# Rauchmelder_2_2B.net
KiCad netlist of a schematic drawn in EAGLE
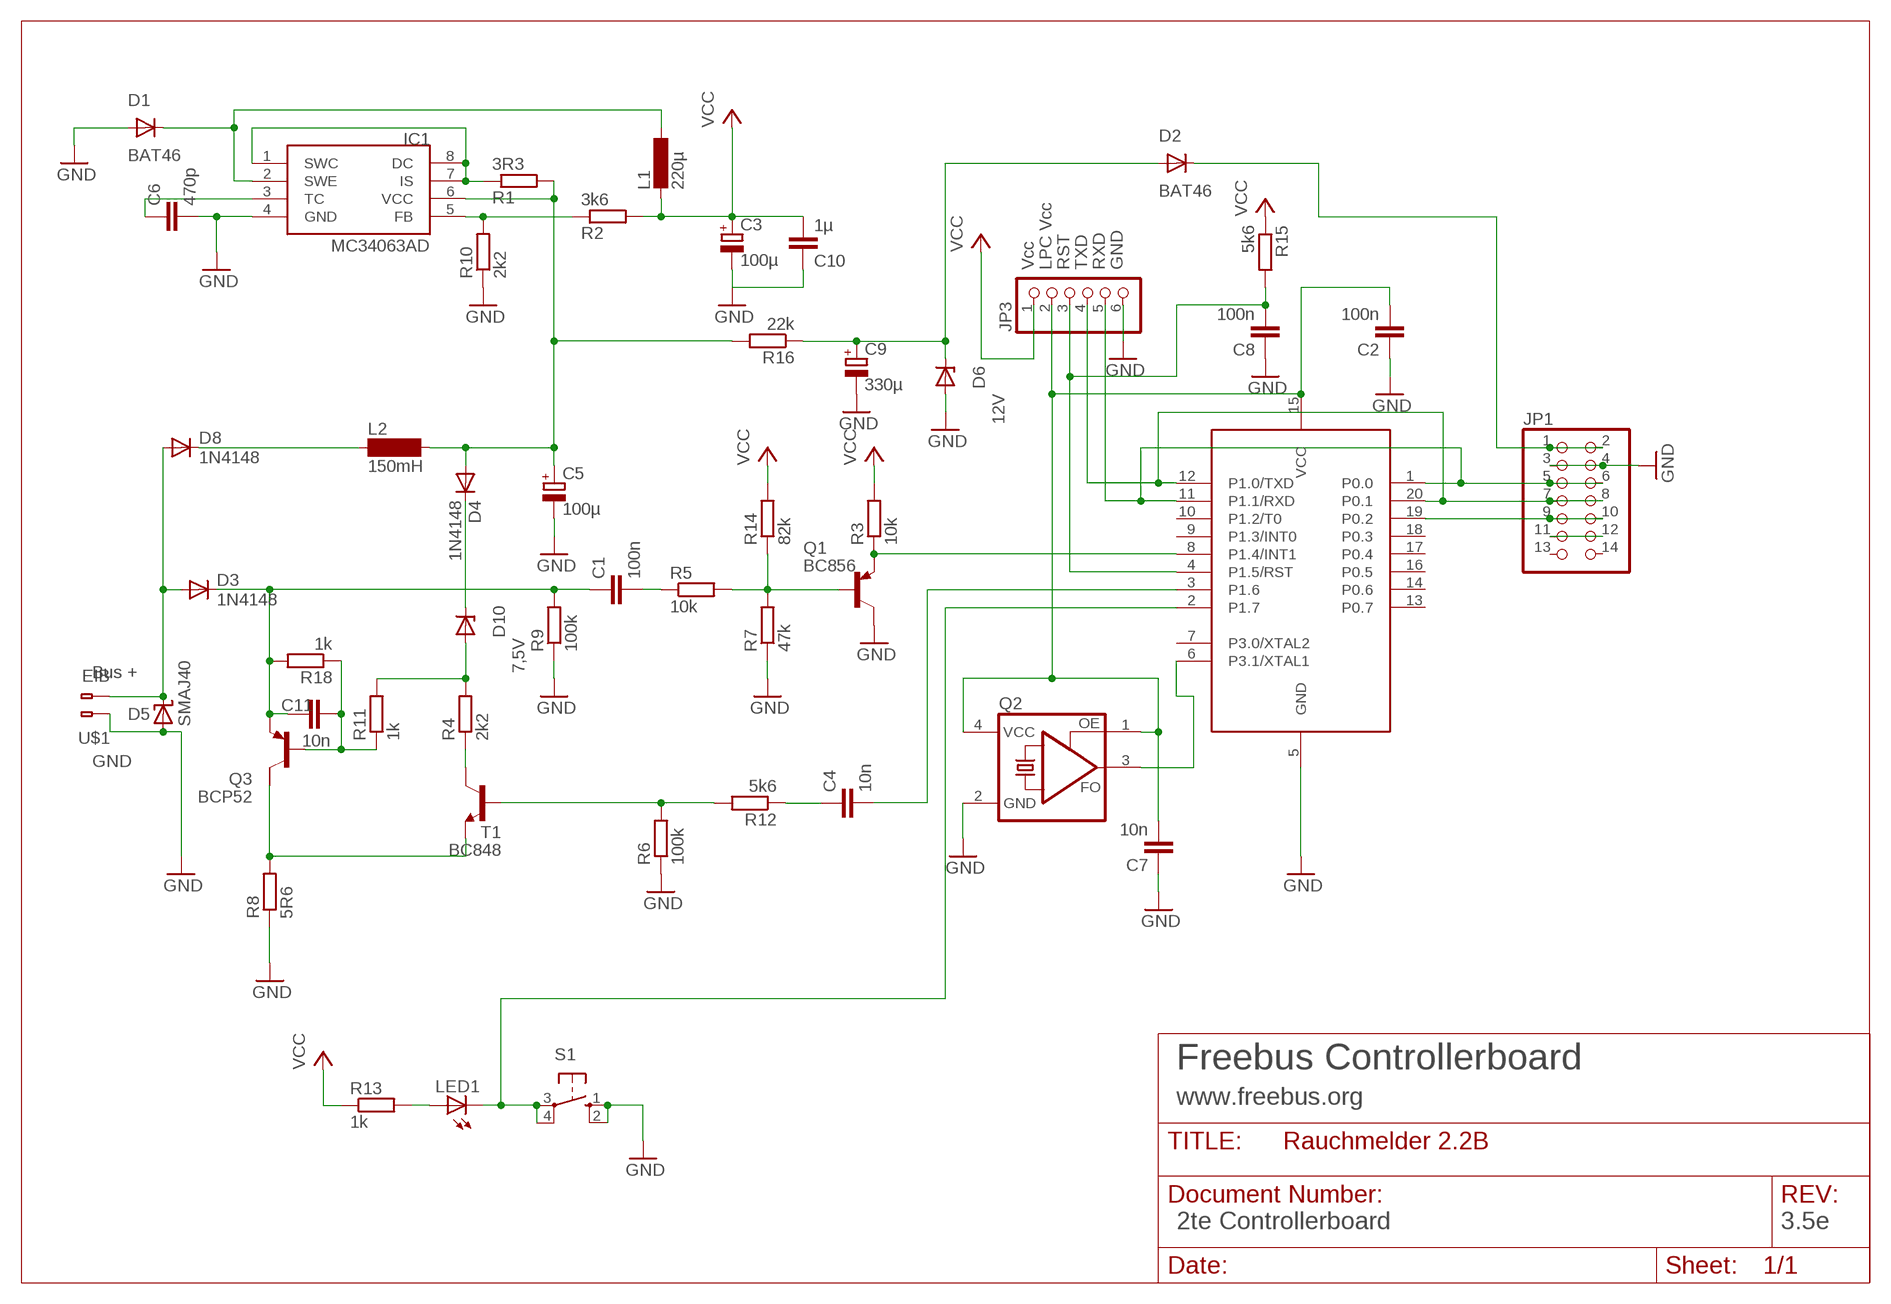
[diagram p0: schematic, sheet 1]

(export (version "E")
  (design (tool "Eeschema 10.0.6"))
  (components
    (comp (ref "C1")
      (value "100n")
      (footprint "eagle-import:C1206")
      (libsource (lib "eagle-import") (part "C-EUC1206"))
    )
    (comp (ref "C2")
      (value "100n")
      (footprint "eagle-import:C1206")
      (libsource (lib "eagle-import") (part "C-EUC1206"))
    )
    (comp (ref "C3")
      (value "100µ")
      (footprint "eagle-import:SANYO-OSCON_SMD_B6")
      (libsource (lib "eagle-import") (part "CPOL-EUSANYO_SMD_B6"))
    )
    (comp (ref "C4")
      (value "10n")
      (footprint "eagle-import:C1206")
      (libsource (lib "eagle-import") (part "C-EUC1206"))
    )
    (comp (ref "C5")
      (value "100µ")
      (footprint "eagle-import:SANYO-OSCON_SMD_C6")
      (libsource (lib "eagle-import") (part "CPOL-EUSANYO_SMD_C6"))
    )
    (comp (ref "C6")
      (value "470p")
      (footprint "eagle-import:C1206")
      (libsource (lib "eagle-import") (part "C-EUC1206"))
    )
    (comp (ref "C7")
      (value "10n")
      (footprint "eagle-import:C1206")
      (libsource (lib "eagle-import") (part "C-EUC1206"))
    )
    (comp (ref "C8")
      (value "100n")
      (footprint "eagle-import:C1206")
      (libsource (lib "eagle-import") (part "C-EUC1206"))
    )
    (comp (ref "C9")
      (value "330µ")
      (footprint "eagle-import:E3,5-8")
      (libsource (lib "eagle-import") (part "CPOL-EUE3.5-8"))
    )
    (comp (ref "C10")
      (value "1µ")
      (footprint "eagle-import:C1206")
      (libsource (lib "eagle-import") (part "C-EUC1206"))
    )
    (comp (ref "C11")
      (value "10n")
      (footprint "eagle-import:C1206")
      (libsource (lib "eagle-import") (part "C-EUC1206"))
    )
    (comp (ref "D1")
      (value "BAT46")
      (footprint "eagle-import:MINIMELF")
      (libsource (lib "eagle-import") (part "DIODE-MINIMELF"))
    )
    (comp (ref "D2")
      (value "BAT46")
      (footprint "eagle-import:MINIMELF")
      (libsource (lib "eagle-import") (part "DIODE-MINIMELF"))
    )
    (comp (ref "D3")
      (value "1N4148")
      (footprint "eagle-import:MINIMELF")
      (libsource (lib "eagle-import") (part "DIODE-MINIMELF"))
    )
    (comp (ref "D4")
      (value "1N4148")
      (footprint "eagle-import:MINIMELF")
      (libsource (lib "eagle-import") (part "DIODE-MINIMELF"))
    )
    (comp (ref "D5")
      (value "SMAJ40")
      (footprint "eagle-import:SMBJ")
      (libsource (lib "eagle-import") (part "SUPPRESSOR-SMBJ"))
    )
    (comp (ref "D6")
      (value "12V")
      (footprint "eagle-import:MINIMELF")
      (libsource (lib "eagle-import") (part "ZPD"))
    )
    (comp (ref "D8")
      (value "1N4148")
      (footprint "eagle-import:MINIMELF")
      (libsource (lib "eagle-import") (part "DIODE-MINIMELF"))
    )
    (comp (ref "D10")
      (value "7,5V")
      (footprint "eagle-import:MINIMELF")
      (libsource (lib "eagle-import") (part "ZPD"))
    )
    (comp (ref "IC1")
      (value "MC34063AD")
      (footprint "eagle-import:SOIC8")
      (libsource (lib "eagle-import") (part "MC34063AD"))
    )
    (comp (ref "IC3")
      (value "LPC922FDH")
      (footprint "eagle-import:TSSOP20")
      (libsource (lib "eagle-import") (part "LPC922FDH"))
    )
    (comp (ref "JP1")
      (value "PINHD-2X7")
      (footprint "eagle-import:2X07")
      (libsource (lib "eagle-import") (part "PINHD-2X7"))
    )
    (comp (ref "JP3")
      (value "PINHD-1X6")
      (footprint "eagle-import:1X06")
      (libsource (lib "eagle-import") (part "PINHD-1X6"))
    )
    (comp (ref "L1")
      (value "220µ")
      (footprint "eagle-import:0207_10")
      (libsource (lib "eagle-import") (part "L-EU0207/10"))
    )
    (comp (ref "L2")
      (value "150mH")
      (footprint "eagle-import:BS11")
      (libsource (lib "eagle-import") (part "BS11"))
    )
    (comp (ref "LED1")
      (value "LED3MM")
      (footprint "eagle-import:LED3MM")
      (libsource (lib "eagle-import") (part "LED3MM"))
    )
    (comp (ref "Q1")
      (value "BC856")
      (footprint "eagle-import:SOT23-BEC")
      (libsource (lib "eagle-import") (part "BC856SMDALT1"))
    )
    (comp (ref "Q2")
      (value "ASFL")
      (footprint "eagle-import:ASF")
      (libsource (lib "eagle-import") (part "ASFL"))
    )
    (comp (ref "Q3")
      (value "BCP52")
      (footprint "eagle-import:SOT223")
      (libsource (lib "eagle-import") (part "FZT753SMD"))
    )
    (comp (ref "R1")
      (value "3R3")
      (footprint "eagle-import:R1206")
      (libsource (lib "eagle-import") (part "R-EU_R1206"))
    )
    (comp (ref "R2")
      (value "3k6")
      (footprint "eagle-import:R1206")
      (libsource (lib "eagle-import") (part "R-EU_R1206"))
    )
    (comp (ref "R3")
      (value "10k")
      (footprint "eagle-import:R1206")
      (libsource (lib "eagle-import") (part "R-EU_R1206"))
    )
    (comp (ref "R4")
      (value "2k2")
      (footprint "eagle-import:R1206")
      (libsource (lib "eagle-import") (part "R-EU_R1206"))
    )
    (comp (ref "R5")
      (value "10k")
      (footprint "eagle-import:R1206")
      (libsource (lib "eagle-import") (part "R-EU_R1206"))
    )
    (comp (ref "R6")
      (value "100k")
      (footprint "eagle-import:R1206")
      (libsource (lib "eagle-import") (part "R-EU_R1206"))
    )
    (comp (ref "R7")
      (value "47k")
      (footprint "eagle-import:R1206")
      (libsource (lib "eagle-import") (part "R-EU_R1206"))
    )
    (comp (ref "R8")
      (value "5R6")
      (footprint "eagle-import:R1206")
      (libsource (lib "eagle-import") (part "R-EU_R1206"))
    )
    (comp (ref "R9")
      (value "100k")
      (footprint "eagle-import:R1206")
      (libsource (lib "eagle-import") (part "R-EU_R1206"))
    )
    (comp (ref "R10")
      (value "2k2")
      (footprint "eagle-import:R1206")
      (libsource (lib "eagle-import") (part "R-EU_R1206"))
    )
    (comp (ref "R11")
      (value "1k")
      (footprint "eagle-import:R1206")
      (libsource (lib "eagle-import") (part "R-EU_R1206"))
    )
    (comp (ref "R12")
      (value "5k6")
      (footprint "eagle-import:R1206")
      (libsource (lib "eagle-import") (part "R-EU_R1206"))
    )
    (comp (ref "R13")
      (value "1k")
      (footprint "eagle-import:R1206")
      (libsource (lib "eagle-import") (part "R-EU_R1206"))
    )
    (comp (ref "R14")
      (value "82k")
      (footprint "eagle-import:R1206")
      (libsource (lib "eagle-import") (part "R-EU_R1206"))
    )
    (comp (ref "R15")
      (value "5k6")
      (footprint "eagle-import:R1206")
      (libsource (lib "eagle-import") (part "R-EU_R1206"))
    )
    (comp (ref "R16")
      (value "22k")
      (footprint "eagle-import:R1206")
      (libsource (lib "eagle-import") (part "R-EU_R1206"))
    )
    (comp (ref "R18")
      (value "1k")
      (footprint "eagle-import:R1206")
      (libsource (lib "eagle-import") (part "R-EU_R1206"))
    )
    (comp (ref "S1")
      (value "10-XX")
      (footprint "eagle-import:B3F-10XX")
      (libsource (lib "eagle-import") (part "10-XX"))
    )
    (comp (ref "T1")
      (value "BC848")
      (footprint "eagle-import:SOT23")
      (libsource (lib "eagle-import") (part "BC848"))
    )
    (comp (ref "U$1")
      (value "EIB")
      (footprint "eagle-import:BUSKLEMME243-724")
      (libsource (lib "eagle-import") (part "EIB"))
    )
  )
  (nets
    (net (code "1") (name "GND") (class "Default")
      (node (ref "C10") (pin "1") (pinfunction "1_1") (pintype "passive"))
      (node (ref "C2") (pin "1") (pinfunction "1_1") (pintype "passive"))
      (node (ref "C3") (pin "-") (pinfunction "-_-") (pintype "passive"))
      (node (ref "C5") (pin "-") (pinfunction "-_-") (pintype "passive"))
      (node (ref "C6") (pin "2") (pinfunction "2_2") (pintype "passive"))
      (node (ref "C7") (pin "1") (pinfunction "1_1") (pintype "passive"))
      (node (ref "C8") (pin "1") (pinfunction "1_1") (pintype "passive"))
      (node (ref "C9") (pin "-") (pinfunction "-_-") (pintype "passive"))
      (node (ref "D1") (pin "A") (pinfunction "A_A") (pintype "passive"))
      (node (ref "D5") (pin "A") (pinfunction "A_A") (pintype "passive"))
      (node (ref "D6") (pin "A") (pinfunction "A_A") (pintype "passive"))
      (node (ref "IC1") (pin "4") (pinfunction "GND_4") (pintype "passive"))
      (node (ref "IC3") (pin "5") (pinfunction "GND_5") (pintype "bidirectional"))
      (node (ref "JP1") (pin "3") (pinfunction "3_3") (pintype "passive"))
      (node (ref "JP1") (pin "4") (pinfunction "4_4") (pintype "passive"))
      (node (ref "JP3") (pin "6") (pinfunction "6_6") (pintype "passive"))
      (node (ref "Q1") (pin "C") (pinfunction "C_C") (pintype "passive"))
      (node (ref "Q2") (pin "2") (pinfunction "GND_2") (pintype "power_in"))
      (node (ref "R10") (pin "1") (pinfunction "1_1") (pintype "passive"))
      (node (ref "R6") (pin "1") (pinfunction "1_1") (pintype "passive"))
      (node (ref "R7") (pin "1") (pinfunction "1_1") (pintype "passive"))
      (node (ref "R8") (pin "1") (pinfunction "1_1") (pintype "passive"))
      (node (ref "R9") (pin "1") (pinfunction "1_1") (pintype "passive"))
      (node (ref "S1") (pin "1") (pinfunction "S_1") (pintype "passive"))
      (node (ref "S1") (pin "2") (pinfunction "S1_2") (pintype "passive"))
      (node (ref "U$1") (pin "1") (pinfunction "B-1_1") (pintype "passive"))
    )
    (net (code "2") (name "Net-(C1-Pad2)") (class "Default")
      (node (ref "C1") (pin "2") (pinfunction "2_2") (pintype "passive"))
      (node (ref "R5") (pin "1") (pinfunction "1_1") (pintype "passive"))
    )
    (net (code "3") (name "Net-(C4-Pad1)") (class "Default")
      (node (ref "C4") (pin "1") (pinfunction "1_1") (pintype "passive"))
      (node (ref "R12") (pin "1") (pinfunction "1_1") (pintype "passive"))
    )
    (net (code "4") (name "Net-(C9-Pad+)") (class "Default")
      (node (ref "C9") (pin "+") (pinfunction "+_+") (pintype "passive"))
      (node (ref "D2") (pin "A") (pinfunction "A_A") (pintype "passive"))
      (node (ref "D6") (pin "C") (pinfunction "C_C") (pintype "passive"))
      (node (ref "R16") (pin "1") (pinfunction "1_1") (pintype "passive"))
    )
    (net (code "5") (name "Net-(D2-PadC)") (class "Default")
      (node (ref "D2") (pin "C") (pinfunction "C_C") (pintype "passive"))
      (node (ref "JP1") (pin "1") (pinfunction "1_1") (pintype "passive"))
      (node (ref "JP1") (pin "2") (pinfunction "2_2") (pintype "passive"))
    )
    (net (code "6") (name "Net-(D8-PadC)") (class "Default")
      (node (ref "D8") (pin "C") (pinfunction "C_C") (pintype "passive"))
      (node (ref "L2") (pin "1") (pinfunction "1_1") (pintype "passive"))
    )
    (net (code "7") (name "Net-(D10-PadA)") (class "Default")
      (node (ref "D10") (pin "A") (pinfunction "A_A") (pintype "passive"))
      (node (ref "R11") (pin "2") (pinfunction "2_2") (pintype "passive"))
      (node (ref "R4") (pin "2") (pinfunction "2_2") (pintype "passive"))
    )
    (net (code "8") (name "Net-(D10-PadC)") (class "Default")
      (node (ref "D10") (pin "C") (pinfunction "C_C") (pintype "passive"))
      (node (ref "D4") (pin "C") (pinfunction "C_C") (pintype "passive"))
    )
    (net (code "9") (name "Net-(IC1-DC)") (class "Default")
      (node (ref "IC1") (pin "1") (pinfunction "SWC_1") (pintype "passive"))
      (node (ref "IC1") (pin "7") (pinfunction "IS_7") (pintype "passive"))
      (node (ref "IC1") (pin "8") (pinfunction "DC_8") (pintype "passive"))
      (node (ref "R1") (pin "1") (pinfunction "1_1") (pintype "passive"))
    )
    (net (code "10") (name "Net-(IC1-FB)") (class "Default")
      (node (ref "IC1") (pin "5") (pinfunction "FB_5") (pintype "passive"))
      (node (ref "R10") (pin "2") (pinfunction "2_2") (pintype "passive"))
      (node (ref "R2") (pin "1") (pinfunction "1_1") (pintype "passive"))
    )
    (net (code "11") (name "Net-(IC1-SWE)") (class "Default")
      (node (ref "D1") (pin "C") (pinfunction "C_C") (pintype "passive"))
      (node (ref "IC1") (pin "2") (pinfunction "SWE_2") (pintype "passive"))
      (node (ref "L1") (pin "1") (pinfunction "1_1") (pintype "passive"))
    )
    (net (code "12") (name "Net-(IC1-TC)") (class "Default")
      (node (ref "C6") (pin "1") (pinfunction "1_1") (pintype "passive"))
      (node (ref "IC1") (pin "3") (pinfunction "TC_3") (pintype "passive"))
    )
    (net (code "13") (name "Net-(IC1-VCC)") (class "Default")
      (node (ref "C5") (pin "+") (pinfunction "+_+") (pintype "passive"))
      (node (ref "D4") (pin "A") (pinfunction "A_A") (pintype "passive"))
      (node (ref "IC1") (pin "6") (pinfunction "VCC_6") (pintype "passive"))
      (node (ref "L2") (pin "2") (pinfunction "2_2") (pintype "passive"))
      (node (ref "R1") (pin "2") (pinfunction "2_2") (pintype "passive"))
      (node (ref "R16") (pin "2") (pinfunction "2_2") (pintype "passive"))
    )
    (net (code "14") (name "Net-(IC3-P0.0)") (class "Default")
      (node (ref "IC3") (pin "1") (pinfunction "P0.0_1") (pintype "bidirectional"))
      (node (ref "IC3") (pin "11") (pinfunction "P1.1/RXD_11") (pintype "bidirectional"))
      (node (ref "JP1") (pin "5") (pinfunction "5_5") (pintype "passive"))
      (node (ref "JP1") (pin "6") (pinfunction "6_6") (pintype "passive"))
      (node (ref "JP3") (pin "5") (pinfunction "5_5") (pintype "passive"))
    )
    (net (code "15") (name "Net-(IC3-P0.1)") (class "Default")
      (node (ref "IC3") (pin "12") (pinfunction "P1.0/TXD_12") (pintype "bidirectional"))
      (node (ref "IC3") (pin "20") (pinfunction "P0.1_20") (pintype "bidirectional"))
      (node (ref "JP1") (pin "7") (pinfunction "7_7") (pintype "passive"))
      (node (ref "JP1") (pin "8") (pinfunction "8_8") (pintype "passive"))
      (node (ref "JP3") (pin "4") (pinfunction "4_4") (pintype "passive"))
    )
    (net (code "16") (name "Net-(IC3-P0.2)") (class "Default")
      (node (ref "IC3") (pin "19") (pinfunction "P0.2_19") (pintype "bidirectional"))
      (node (ref "JP1") (pin "10") (pinfunction "10_10") (pintype "passive"))
      (node (ref "JP1") (pin "9") (pinfunction "9_9") (pintype "passive"))
    )
    (net (code "17") (name "Net-(IC3-P1.4{slash}INT1)") (class "Default")
      (node (ref "IC3") (pin "8") (pinfunction "P1.4/INT1_8") (pintype "bidirectional"))
      (node (ref "Q1") (pin "E") (pinfunction "E_E") (pintype "passive"))
      (node (ref "R3") (pin "1") (pinfunction "1_1") (pintype "passive"))
    )
    (net (code "18") (name "Net-(IC3-P1.5{slash}RST)") (class "Default")
      (node (ref "C8") (pin "2") (pinfunction "2_2") (pintype "passive"))
      (node (ref "IC3") (pin "4") (pinfunction "P1.5/RST_4") (pintype "bidirectional"))
      (node (ref "JP3") (pin "3") (pinfunction "3_3") (pintype "passive"))
      (node (ref "R15") (pin "2") (pinfunction "2_2") (pintype "passive"))
    )
    (net (code "19") (name "Net-(IC3-P1.6)") (class "Default")
      (node (ref "C4") (pin "2") (pinfunction "2_2") (pintype "passive"))
      (node (ref "IC3") (pin "3") (pinfunction "P1.6_3") (pintype "bidirectional"))
    )
    (net (code "20") (name "Net-(IC3-P1.7)") (class "Default")
      (node (ref "IC3") (pin "2") (pinfunction "P1.7_2") (pintype "bidirectional"))
      (node (ref "LED1") (pin "K") (pinfunction "C_K") (pintype "passive"))
      (node (ref "S1") (pin "3") (pinfunction "P_3") (pintype "passive"))
      (node (ref "S1") (pin "4") (pinfunction "P1_4") (pintype "passive"))
    )
    (net (code "21") (name "Net-(IC3-P3.1{slash}XTAL1)") (class "Default")
      (node (ref "IC3") (pin "6") (pinfunction "P3.1/XTAL1_6") (pintype "bidirectional"))
      (node (ref "Q2") (pin "3") (pinfunction "FO_3") (pintype "output"))
    )
    (net (code "22") (name "Net-(IC3-VCC)") (class "Default")
      (node (ref "C2") (pin "2") (pinfunction "2_2") (pintype "passive"))
      (node (ref "C7") (pin "2") (pinfunction "2_2") (pintype "passive"))
      (node (ref "IC3") (pin "15") (pinfunction "VCC_15") (pintype "bidirectional"))
      (node (ref "JP3") (pin "2") (pinfunction "2_2") (pintype "passive"))
      (node (ref "Q2") (pin "1") (pinfunction "OE_1") (pintype "input"))
      (node (ref "Q2") (pin "4") (pinfunction "VCC_4") (pintype "power_in"))
    )
    (net (code "23") (name "Net-(JP1-Pad11)") (class "Default")
      (node (ref "JP1") (pin "11") (pinfunction "11_11") (pintype "passive"))
      (node (ref "JP1") (pin "12") (pinfunction "12_12") (pintype "passive"))
    )
    (net (code "24") (name "Net-(LED1-PadA)") (class "Default")
      (node (ref "LED1") (pin "A") (pinfunction "A_A") (pintype "passive"))
      (node (ref "R13") (pin "2") (pinfunction "2_2") (pintype "passive"))
    )
    (net (code "25") (name "Net-(Q1-PadB)") (class "Default")
      (node (ref "Q1") (pin "B") (pinfunction "B_B") (pintype "passive"))
      (node (ref "R14") (pin "1") (pinfunction "1_1") (pintype "passive"))
      (node (ref "R5") (pin "2") (pinfunction "2_2") (pintype "passive"))
      (node (ref "R7") (pin "2") (pinfunction "2_2") (pintype "passive"))
    )
    (net (code "26") (name "Net-(Q3-B)") (class "Default")
      (node (ref "C11") (pin "2") (pinfunction "2_2") (pintype "passive"))
      (node (ref "Q3") (pin "1") (pinfunction "B_1") (pintype "passive"))
      (node (ref "R11") (pin "1") (pinfunction "1_1") (pintype "passive"))
      (node (ref "R18") (pin "1") (pinfunction "1_1") (pintype "passive"))
    )
    (net (code "27") (name "Net-(Q3-C)") (class "Default")
      (node (ref "Q3") (pin "2") (pinfunction "C_2") (pintype "passive"))
      (node (ref "R8") (pin "2") (pinfunction "2_2") (pintype "passive"))
      (node (ref "T1") (pin "2") (pinfunction "E_2") (pintype "passive"))
    )
    (net (code "28") (name "Net-(Q3-E)") (class "Default")
      (node (ref "C1") (pin "1") (pinfunction "1_1") (pintype "passive"))
      (node (ref "C11") (pin "1") (pinfunction "1_1") (pintype "passive"))
      (node (ref "D3") (pin "C") (pinfunction "C_C") (pintype "passive"))
      (node (ref "Q3") (pin "3") (pinfunction "E_3") (pintype "passive"))
      (node (ref "R18") (pin "2") (pinfunction "2_2") (pintype "passive"))
      (node (ref "R9") (pin "2") (pinfunction "2_2") (pintype "passive"))
    )
    (net (code "29") (name "Net-(T1-B)") (class "Default")
      (node (ref "R12") (pin "2") (pinfunction "2_2") (pintype "passive"))
      (node (ref "R6") (pin "2") (pinfunction "2_2") (pintype "passive"))
      (node (ref "T1") (pin "1") (pinfunction "B_1") (pintype "passive"))
    )
    (net (code "30") (name "Net-(T1-C)") (class "Default")
      (node (ref "R4") (pin "1") (pinfunction "1_1") (pintype "passive"))
      (node (ref "T1") (pin "3") (pinfunction "C_3") (pintype "passive"))
    )
    (net (code "31") (name "Net-(U$1-B-2)") (class "Default")
      (node (ref "D3") (pin "A") (pinfunction "A_A") (pintype "passive"))
      (node (ref "D5") (pin "C") (pinfunction "C_C") (pintype "passive"))
      (node (ref "D8") (pin "A") (pinfunction "A_A") (pintype "passive"))
      (node (ref "U$1") (pin "2") (pinfunction "B-2_2") (pintype "passive"))
    )
    (net (code "32") (name "VCC") (class "Default")
      (node (ref "C10") (pin "2") (pinfunction "2_2") (pintype "passive"))
      (node (ref "C3") (pin "+") (pinfunction "+_+") (pintype "passive"))
      (node (ref "JP3") (pin "1") (pinfunction "1_1") (pintype "passive"))
      (node (ref "L1") (pin "2") (pinfunction "2_2") (pintype "passive"))
      (node (ref "R13") (pin "1") (pinfunction "1_1") (pintype "passive"))
      (node (ref "R14") (pin "2") (pinfunction "2_2") (pintype "passive"))
      (node (ref "R15") (pin "1") (pinfunction "1_1") (pintype "passive"))
      (node (ref "R2") (pin "2") (pinfunction "2_2") (pintype "passive"))
      (node (ref "R3") (pin "2") (pinfunction "2_2") (pintype "passive"))
    )
    (net (code "33") (name "unconnected-(IC3-P0.3-Pad18)") (class "Default")
      (node (ref "IC3") (pin "18") (pinfunction "P0.3_18") (pintype "bidirectional"))
    )
    (net (code "34") (name "unconnected-(IC3-P0.4-Pad17)") (class "Default")
      (node (ref "IC3") (pin "17") (pinfunction "P0.4_17") (pintype "bidirectional"))
    )
    (net (code "35") (name "unconnected-(IC3-P0.5-Pad16)") (class "Default")
      (node (ref "IC3") (pin "16") (pinfunction "P0.5_16") (pintype "bidirectional"))
    )
    (net (code "36") (name "unconnected-(IC3-P0.6-Pad14)") (class "Default")
      (node (ref "IC3") (pin "14") (pinfunction "P0.6_14") (pintype "bidirectional"))
    )
    (net (code "37") (name "unconnected-(IC3-P0.7-Pad13)") (class "Default")
      (node (ref "IC3") (pin "13") (pinfunction "P0.7_13") (pintype "bidirectional"))
    )
    (net (code "38") (name "unconnected-(IC3-P1.2{slash}T0-Pad10)") (class "Default")
      (node (ref "IC3") (pin "10") (pinfunction "P1.2/T0_10") (pintype "bidirectional"))
    )
    (net (code "39") (name "unconnected-(IC3-P1.3{slash}INT0-Pad9)") (class "Default")
      (node (ref "IC3") (pin "9") (pinfunction "P1.3/INT0_9") (pintype "bidirectional"))
    )
    (net (code "40") (name "unconnected-(IC3-P3.0{slash}XTAL2-Pad7)") (class "Default")
      (node (ref "IC3") (pin "7") (pinfunction "P3.0/XTAL2_7") (pintype "bidirectional"))
    )
    (net (code "41") (name "unconnected-(JP1-Pad13)") (class "Default")
      (node (ref "JP1") (pin "13") (pinfunction "13_13") (pintype "passive"))
    )
    (net (code "42") (name "unconnected-(JP1-Pad14)") (class "Default")
      (node (ref "JP1") (pin "14") (pinfunction "14_14") (pintype "passive"))
    )
    (net (code "43") (name "unconnected-(Q3-C{slash}-Pad4)") (class "Default")
      (node (ref "Q3") (pin "4") (pinfunction "C/_4") (pintype "passive"))
    )
  )
)
